# ctrlr_w_MCP23008.net
KiCad netlist of a schematic drawn in EAGLE
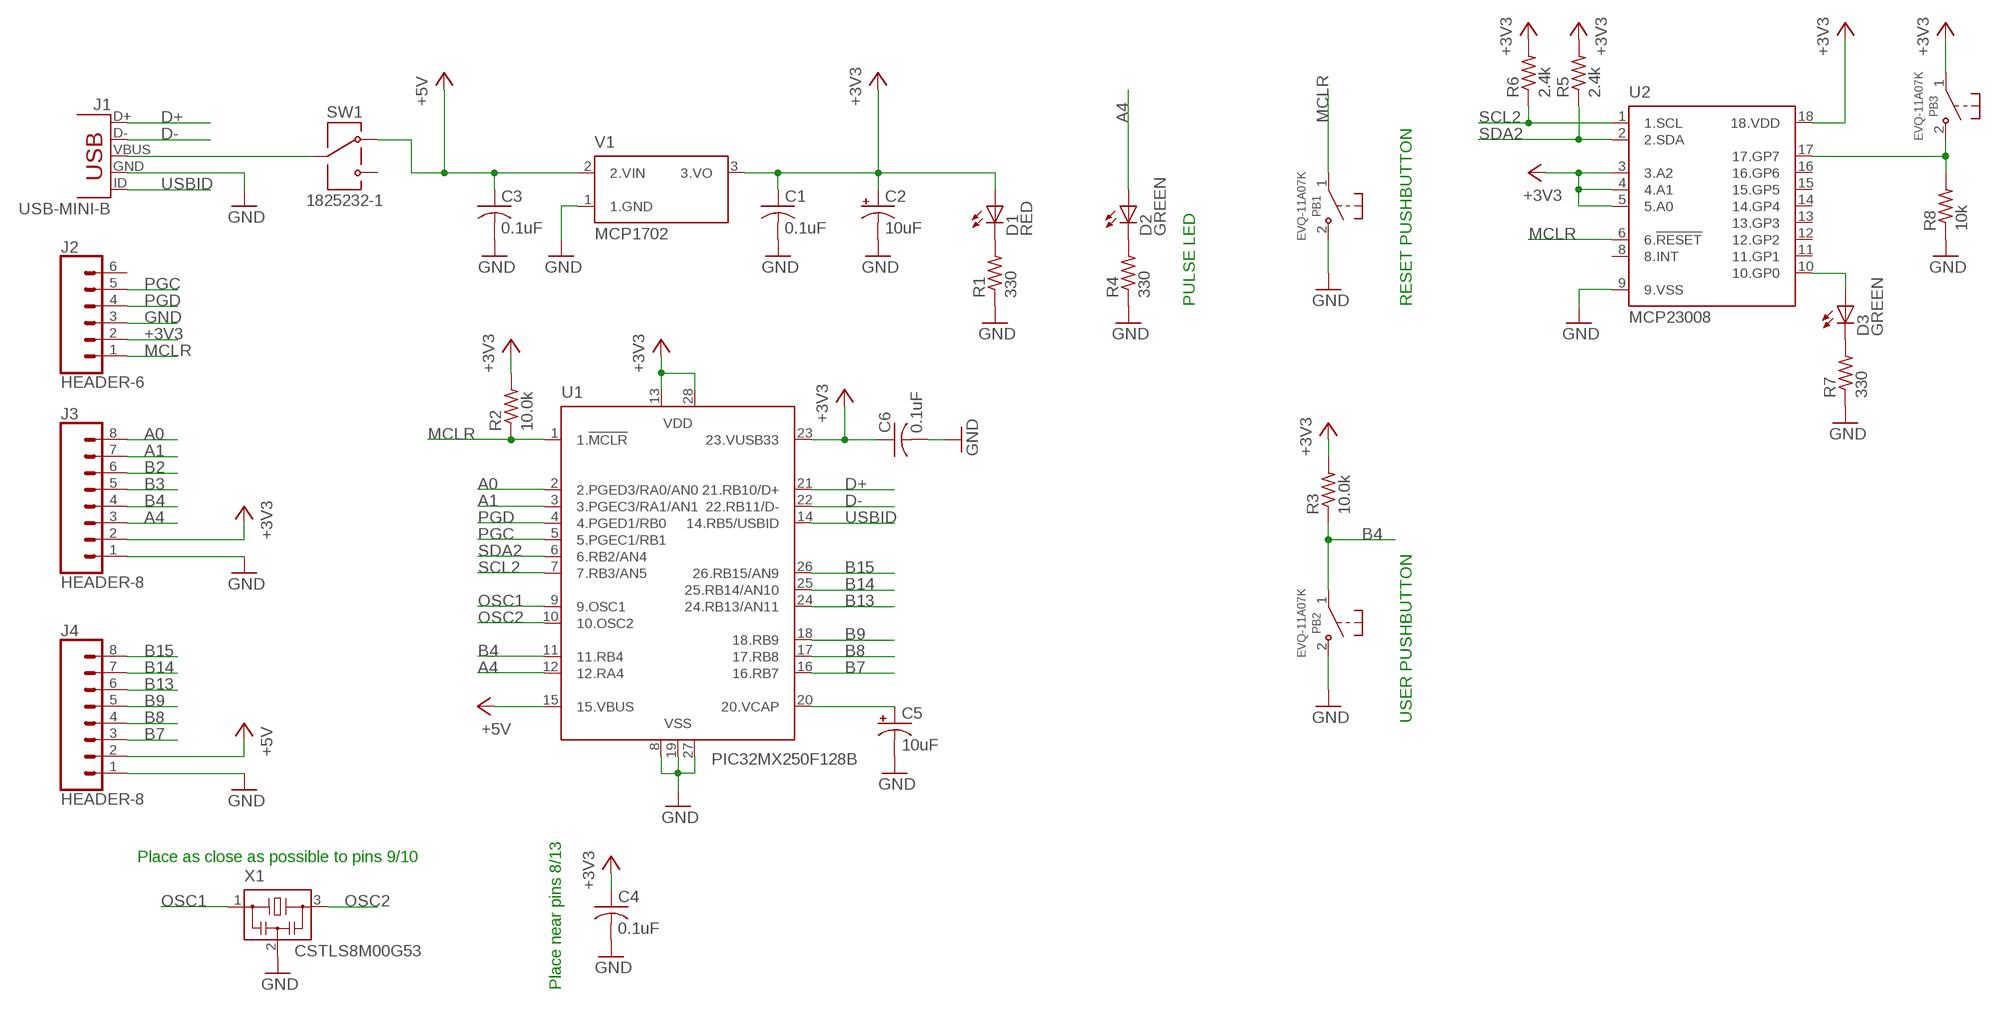
[diagram p0: schematic, sheet 1]

(export (version "E")
  (design (tool "Eeschema 10.0.6"))
  (components
    (comp (ref "C1")
      (value "0.1uF")
      (footprint "eagle-import:C1206")
      (libsource (lib "eagle-import") (part "C-USC1206"))
    )
    (comp (ref "C2")
      (value "10uF")
      (footprint "eagle-import:TAP5-50")
      (libsource (lib "eagle-import") (part "CPOL-USTAP5-50"))
    )
    (comp (ref "C3")
      (value "0.1uF")
      (footprint "eagle-import:C1206")
      (libsource (lib "eagle-import") (part "C-USC1206"))
    )
    (comp (ref "C4")
      (value "0.1uF")
      (footprint "eagle-import:C1206")
      (libsource (lib "eagle-import") (part "C-USC1206"))
    )
    (comp (ref "C5")
      (value "10uF")
      (footprint "eagle-import:TAP5-50")
      (libsource (lib "eagle-import") (part "CPOL-USTAP5-50"))
    )
    (comp (ref "C6")
      (value "0.1uF")
      (footprint "eagle-import:C1206")
      (libsource (lib "eagle-import") (part "C-USC1206"))
    )
    (comp (ref "D1")
      (value "LED-RED")
      (footprint "eagle-import:LED-3MM-V")
      (libsource (lib "eagle-import") (part "LED-RED"))
    )
    (comp (ref "D2")
      (value "LED-GREEN")
      (footprint "eagle-import:LED-3MM-V")
      (libsource (lib "eagle-import") (part "LED-GREEN"))
    )
    (comp (ref "D3")
      (value "LED-GREEN")
      (footprint "eagle-import:LED-3MM-V")
      (libsource (lib "eagle-import") (part "LED-GREEN"))
    )
    (comp (ref "J1")
      (value "USB-MINI-B")
      (footprint "eagle-import:USB-MB-TO")
      (libsource (lib "eagle-import") (part "USB-MINI-B"))
    )
    (comp (ref "J2")
      (value "HEADER-6")
      (footprint "eagle-import:CONN_1X06")
      (libsource (lib "eagle-import") (part "HEADER-6"))
    )
    (comp (ref "J3")
      (value "HEADER-8")
      (footprint "eagle-import:CONN_1X08")
      (libsource (lib "eagle-import") (part "HEADER-8"))
    )
    (comp (ref "J4")
      (value "HEADER-8")
      (footprint "eagle-import:CONN_1X08")
      (libsource (lib "eagle-import") (part "HEADER-8"))
    )
    (comp (ref "PB1")
      (value "EVQ-11A07K")
      (footprint "eagle-import:PCPIN-2")
      (libsource (lib "eagle-import") (part "EVQ-11A07K"))
    )
    (comp (ref "PB2")
      (value "EVQ-11A07K")
      (footprint "eagle-import:PCPIN-2")
      (libsource (lib "eagle-import") (part "EVQ-11A07K"))
    )
    (comp (ref "PB3")
      (value "EVQ-11A07K")
      (footprint "eagle-import:PCPIN-2")
      (libsource (lib "eagle-import") (part "EVQ-11A07K"))
    )
    (comp (ref "R1")
      (value "330")
      (footprint "eagle-import:R1206")
      (libsource (lib "eagle-import") (part "R-US_R1206"))
    )
    (comp (ref "R2")
      (value "10.0k")
      (footprint "eagle-import:R1206")
      (libsource (lib "eagle-import") (part "R-US_R1206"))
    )
    (comp (ref "R3")
      (value "10.0k")
      (footprint "eagle-import:R1206")
      (libsource (lib "eagle-import") (part "R-US_R1206"))
    )
    (comp (ref "R4")
      (value "330")
      (footprint "eagle-import:R1206")
      (libsource (lib "eagle-import") (part "R-US_R1206"))
    )
    (comp (ref "R5")
      (value "2.4k")
      (footprint "eagle-import:R1206")
      (libsource (lib "eagle-import") (part "R-US_R1206"))
    )
    (comp (ref "R6")
      (value "2.4k")
      (footprint "eagle-import:R1206")
      (libsource (lib "eagle-import") (part "R-US_R1206"))
    )
    (comp (ref "R7")
      (value "330")
      (footprint "eagle-import:R1206")
      (libsource (lib "eagle-import") (part "R-US_R1206"))
    )
    (comp (ref "R8")
      (value "10k")
      (footprint "eagle-import:R1206")
      (libsource (lib "eagle-import") (part "R-US_R1206"))
    )
    (comp (ref "SW1")
      (value "1825232-1")
      (footprint "eagle-import:PCPIN-3SS")
      (libsource (lib "eagle-import") (part "1825232-1"))
    )
    (comp (ref "U1")
      (value "PIC32MX250F128B")
      (footprint "eagle-import:DIP28-3")
      (libsource (lib "eagle-import") (part "PIC32MX250F128B"))
    )
    (comp (ref "U2")
      (value "MCP23008")
      (footprint "eagle-import:DIP18")
      (libsource (lib "eagle-import") (part "MCP23008"))
    )
    (comp (ref "V1")
      (value "MCP1702")
      (footprint "eagle-import:TO-92")
      (libsource (lib "eagle-import") (part "MCP1702"))
    )
    (comp (ref "X1")
      (value "CSTLS8M00G53")
      (footprint "eagle-import:RAD-3-2.5")
      (libsource (lib "eagle-import") (part "CSTLS8M00G53"))
    )
  )
  (nets
    (net (code "1") (name "+3V3") (class "Default")
      (node (ref "C1") (pin "1") (pinfunction "1_1") (pintype "passive"))
      (node (ref "C2") (pin "+") (pinfunction "+_+") (pintype "passive"))
      (node (ref "C4") (pin "1") (pinfunction "1_1") (pintype "passive"))
      (node (ref "C6") (pin "1") (pinfunction "1_1") (pintype "passive"))
      (node (ref "D1") (pin "A") (pinfunction "A_A") (pintype "passive"))
      (node (ref "J2") (pin "2") (pinfunction "2._2") (pintype "passive"))
      (node (ref "J3") (pin "2") (pinfunction "2._2") (pintype "passive"))
      (node (ref "PB3") (pin "1") (pinfunction "1.A_1") (pintype "bidirectional"))
      (node (ref "R2") (pin "2") (pinfunction "2_2") (pintype "passive"))
      (node (ref "R3") (pin "2") (pinfunction "2_2") (pintype "passive"))
      (node (ref "R5") (pin "2") (pinfunction "2_2") (pintype "passive"))
      (node (ref "R6") (pin "2") (pinfunction "2_2") (pintype "passive"))
      (node (ref "U1") (pin "13") (pinfunction "13.VDD_13") (pintype "power_in"))
      (node (ref "U1") (pin "23") (pinfunction "23.VUSB33_23") (pintype "bidirectional"))
      (node (ref "U1") (pin "28") (pinfunction "28.AVDD_28") (pintype "power_in"))
      (node (ref "U2") (pin "18") (pinfunction "18.VDD_18") (pintype "input"))
      (node (ref "U2") (pin "3") (pinfunction "3.A2_3") (pintype "input"))
      (node (ref "U2") (pin "4") (pinfunction "4.A1_4") (pintype "input"))
      (node (ref "U2") (pin "5") (pinfunction "5.A0_5") (pintype "input"))
      (node (ref "V1") (pin "3") (pinfunction "3.VO_3") (pintype "output"))
    )
    (net (code "2") (name "+5V") (class "Default")
      (node (ref "C3") (pin "1") (pinfunction "1_1") (pintype "passive"))
      (node (ref "J4") (pin "2") (pinfunction "2._2") (pintype "passive"))
      (node (ref "SW1") (pin "1") (pinfunction "1_1") (pintype "bidirectional"))
      (node (ref "U1") (pin "15") (pinfunction "15.VBUS_15") (pintype "bidirectional"))
      (node (ref "V1") (pin "2") (pinfunction "2.VIN_2") (pintype "input"))
    )
    (net (code "3") (name "/A0") (class "Default")
      (node (ref "J3") (pin "8") (pinfunction "8._8") (pintype "passive"))
      (node (ref "U1") (pin "2") (pinfunction "2.PGED3/RA0/AN0_2") (pintype "bidirectional"))
    )
    (net (code "4") (name "/A1") (class "Default")
      (node (ref "J3") (pin "7") (pinfunction "7._7") (pintype "passive"))
      (node (ref "U1") (pin "3") (pinfunction "3.PGEC3/RA1/AN1_3") (pintype "bidirectional"))
    )
    (net (code "5") (name "/A4") (class "Default")
      (node (ref "D2") (pin "A") (pinfunction "A_A") (pintype "passive"))
      (node (ref "J3") (pin "3") (pinfunction "3._3") (pintype "passive"))
      (node (ref "U1") (pin "12") (pinfunction "12.RA4_12") (pintype "bidirectional"))
    )
    (net (code "6") (name "/B2") (class "Default")
      (node (ref "J3") (pin "6") (pinfunction "6._6") (pintype "passive"))
    )
    (net (code "7") (name "/B3") (class "Default")
      (node (ref "J3") (pin "5") (pinfunction "5._5") (pintype "passive"))
    )
    (net (code "8") (name "/B4") (class "Default")
      (node (ref "J3") (pin "4") (pinfunction "4._4") (pintype "passive"))
      (node (ref "PB2") (pin "1") (pinfunction "1.A_1") (pintype "bidirectional"))
      (node (ref "R3") (pin "1") (pinfunction "1_1") (pintype "passive"))
      (node (ref "U1") (pin "11") (pinfunction "11.RB4_11") (pintype "bidirectional"))
    )
    (net (code "9") (name "/B7") (class "Default")
      (node (ref "J4") (pin "3") (pinfunction "3._3") (pintype "passive"))
      (node (ref "U1") (pin "16") (pinfunction "16.RB7_16") (pintype "bidirectional"))
    )
    (net (code "10") (name "/B8") (class "Default")
      (node (ref "J4") (pin "4") (pinfunction "4._4") (pintype "passive"))
      (node (ref "U1") (pin "17") (pinfunction "17.RB8_17") (pintype "bidirectional"))
    )
    (net (code "11") (name "/B9") (class "Default")
      (node (ref "J4") (pin "5") (pinfunction "5._5") (pintype "passive"))
      (node (ref "U1") (pin "18") (pinfunction "18.RB9_18") (pintype "bidirectional"))
    )
    (net (code "12") (name "/B13") (class "Default")
      (node (ref "J4") (pin "6") (pinfunction "6._6") (pintype "passive"))
      (node (ref "U1") (pin "24") (pinfunction "24.RB13/AN11_24") (pintype "bidirectional"))
    )
    (net (code "13") (name "/B14") (class "Default")
      (node (ref "J4") (pin "7") (pinfunction "7._7") (pintype "passive"))
      (node (ref "U1") (pin "25") (pinfunction "25.RB14/AN10_25") (pintype "bidirectional"))
    )
    (net (code "14") (name "/B15") (class "Default")
      (node (ref "J4") (pin "8") (pinfunction "8._8") (pintype "passive"))
      (node (ref "U1") (pin "26") (pinfunction "26.RB15/AN9_26") (pintype "bidirectional"))
    )
    (net (code "15") (name "/D+") (class "Default")
      (node (ref "J1") (pin "D+") (pinfunction "D+_D+") (pintype "bidirectional"))
      (node (ref "U1") (pin "21") (pinfunction "21.RB10/D+_21") (pintype "bidirectional"))
    )
    (net (code "16") (name "/D-") (class "Default")
      (node (ref "J1") (pin "D-") (pinfunction "D-_D-") (pintype "bidirectional"))
      (node (ref "U1") (pin "22") (pinfunction "22.RB11/D-_22") (pintype "bidirectional"))
    )
    (net (code "17") (name "/MCLR") (class "Default")
      (node (ref "J2") (pin "1") (pinfunction "1._1") (pintype "passive"))
      (node (ref "PB1") (pin "1") (pinfunction "1.A_1") (pintype "bidirectional"))
      (node (ref "R2") (pin "1") (pinfunction "1_1") (pintype "passive"))
      (node (ref "U1") (pin "1") (pinfunction "1.~{MCLR}_1") (pintype "input"))
      (node (ref "U2") (pin "6") (pinfunction "6.~{RESET}_6") (pintype "input"))
    )
    (net (code "18") (name "/OSC1") (class "Default")
      (node (ref "U1") (pin "9") (pinfunction "9.OSC1_9") (pintype "input"))
      (node (ref "X1") (pin "1") (pinfunction "1_1") (pintype "passive"))
    )
    (net (code "19") (name "/OSC2") (class "Default")
      (node (ref "U1") (pin "10") (pinfunction "10.OSC2_10") (pintype "output"))
      (node (ref "X1") (pin "3") (pinfunction "3_3") (pintype "passive"))
    )
    (net (code "20") (name "/PGC") (class "Default")
      (node (ref "J2") (pin "5") (pinfunction "5._5") (pintype "passive"))
      (node (ref "U1") (pin "5") (pinfunction "5.PGEC1/RB1_5") (pintype "bidirectional"))
    )
    (net (code "21") (name "/PGD") (class "Default")
      (node (ref "J2") (pin "4") (pinfunction "4._4") (pintype "passive"))
      (node (ref "U1") (pin "4") (pinfunction "4.PGED1/RB0_4") (pintype "bidirectional"))
    )
    (net (code "22") (name "/SCL2") (class "Default")
      (node (ref "R6") (pin "1") (pinfunction "1_1") (pintype "passive"))
      (node (ref "U1") (pin "7") (pinfunction "7.RB3/AN5_7") (pintype "bidirectional"))
      (node (ref "U2") (pin "1") (pinfunction "1.SCL_1") (pintype "input"))
    )
    (net (code "23") (name "/SDA2") (class "Default")
      (node (ref "R5") (pin "1") (pinfunction "1_1") (pintype "passive"))
      (node (ref "U1") (pin "6") (pinfunction "6.RB2/AN4_6") (pintype "bidirectional"))
      (node (ref "U2") (pin "2") (pinfunction "2.SDA_2") (pintype "input"))
    )
    (net (code "24") (name "/USBID") (class "Default")
      (node (ref "J1") (pin "ID") (pinfunction "ID_ID") (pintype "bidirectional"))
      (node (ref "U1") (pin "14") (pinfunction "14.RB5/USBID_14") (pintype "bidirectional"))
    )
    (net (code "25") (name "GND") (class "Default")
      (node (ref "C1") (pin "2") (pinfunction "2_2") (pintype "passive"))
      (node (ref "C2") (pin "-") (pinfunction "-_-") (pintype "passive"))
      (node (ref "C3") (pin "2") (pinfunction "2_2") (pintype "passive"))
      (node (ref "C4") (pin "2") (pinfunction "2_2") (pintype "passive"))
      (node (ref "C5") (pin "-") (pinfunction "-_-") (pintype "passive"))
      (node (ref "C6") (pin "2") (pinfunction "2_2") (pintype "passive"))
      (node (ref "J1") (pin "GND") (pinfunction "GND_GND") (pintype "bidirectional"))
      (node (ref "J2") (pin "3") (pinfunction "3._3") (pintype "passive"))
      (node (ref "J3") (pin "1") (pinfunction "1._1") (pintype "passive"))
      (node (ref "J4") (pin "1") (pinfunction "1._1") (pintype "passive"))
      (node (ref "PB1") (pin "2") (pinfunction "2.B_2") (pintype "bidirectional"))
      (node (ref "PB2") (pin "2") (pinfunction "2.B_2") (pintype "bidirectional"))
      (node (ref "R1") (pin "1") (pinfunction "1_1") (pintype "passive"))
      (node (ref "R4") (pin "1") (pinfunction "1_1") (pintype "passive"))
      (node (ref "R7") (pin "1") (pinfunction "1_1") (pintype "passive"))
      (node (ref "R8") (pin "1") (pinfunction "1_1") (pintype "passive"))
      (node (ref "U1") (pin "19") (pinfunction "19.VSS_19") (pintype "power_in"))
      (node (ref "U1") (pin "27") (pinfunction "27.AVSS_27") (pintype "bidirectional"))
      (node (ref "U1") (pin "8") (pinfunction "8.VSS_8") (pintype "power_in"))
      (node (ref "U2") (pin "9") (pinfunction "9.VSS_9") (pintype "input"))
      (node (ref "V1") (pin "1") (pinfunction "1.GND_1") (pintype "passive"))
      (node (ref "X1") (pin "2") (pinfunction "2_2") (pintype "passive"))
    )
    (net (code "26") (name "Net-(D1-C)") (class "Default")
      (node (ref "D1") (pin "K") (pinfunction "C_K") (pintype "passive"))
      (node (ref "R1") (pin "2") (pinfunction "2_2") (pintype "passive"))
    )
    (net (code "27") (name "Net-(D2-C)") (class "Default")
      (node (ref "D2") (pin "K") (pinfunction "C_K") (pintype "passive"))
      (node (ref "R4") (pin "2") (pinfunction "2_2") (pintype "passive"))
    )
    (net (code "28") (name "Net-(D3-C)") (class "Default")
      (node (ref "D3") (pin "K") (pinfunction "C_K") (pintype "passive"))
      (node (ref "R7") (pin "2") (pinfunction "2_2") (pintype "passive"))
    )
    (net (code "29") (name "Net-(J1-PadVBUS)") (class "Default")
      (node (ref "J1") (pin "VBUS") (pinfunction "VBUS_VBUS") (pintype "bidirectional"))
      (node (ref "SW1") (pin "2") (pinfunction "2_2") (pintype "bidirectional"))
    )
    (net (code "30") (name "Net-(PB3-2.B)") (class "Default")
      (node (ref "PB3") (pin "2") (pinfunction "2.B_2") (pintype "bidirectional"))
      (node (ref "R8") (pin "2") (pinfunction "2_2") (pintype "passive"))
      (node (ref "U2") (pin "17") (pinfunction "17.GP7_17") (pintype "input"))
    )
    (net (code "31") (name "Net-(U1-20.VCAP)") (class "Default")
      (node (ref "C5") (pin "+") (pinfunction "+_+") (pintype "passive"))
      (node (ref "U1") (pin "20") (pinfunction "20.VCAP_20") (pintype "bidirectional"))
    )
    (net (code "32") (name "Net-(U2-10.GP0)") (class "Default")
      (node (ref "D3") (pin "A") (pinfunction "A_A") (pintype "passive"))
      (node (ref "U2") (pin "10") (pinfunction "10.GP0_10") (pintype "input"))
    )
    (net (code "33") (name "unconnected-(J2-6.-Pad6)") (class "Default")
      (node (ref "J2") (pin "6") (pinfunction "6._6") (pintype "passive"))
    )
    (net (code "34") (name "unconnected-(SW1-Pad3)") (class "Default")
      (node (ref "SW1") (pin "3") (pinfunction "3_3") (pintype "bidirectional"))
    )
    (net (code "35") (name "unconnected-(U2-8.INT-Pad8)") (class "Default")
      (node (ref "U2") (pin "8") (pinfunction "8.INT_8") (pintype "input"))
    )
    (net (code "36") (name "unconnected-(U2-11.GP1-Pad11)") (class "Default")
      (node (ref "U2") (pin "11") (pinfunction "11.GP1_11") (pintype "input"))
    )
    (net (code "37") (name "unconnected-(U2-12.GP2-Pad12)") (class "Default")
      (node (ref "U2") (pin "12") (pinfunction "12.GP2_12") (pintype "input"))
    )
    (net (code "38") (name "unconnected-(U2-13.GP3-Pad13)") (class "Default")
      (node (ref "U2") (pin "13") (pinfunction "13.GP3_13") (pintype "input"))
    )
    (net (code "39") (name "unconnected-(U2-14.GP4-Pad14)") (class "Default")
      (node (ref "U2") (pin "14") (pinfunction "14.GP4_14") (pintype "input"))
    )
    (net (code "40") (name "unconnected-(U2-15.GP5-Pad15)") (class "Default")
      (node (ref "U2") (pin "15") (pinfunction "15.GP5_15") (pintype "input"))
    )
    (net (code "41") (name "unconnected-(U2-16.GP6-Pad16)") (class "Default")
      (node (ref "U2") (pin "16") (pinfunction "16.GP6_16") (pintype "input"))
    )
  )
)
